# XBee_nRF53240_1_2_may_2022.net
KiCad netlist of a schematic drawn in EAGLE
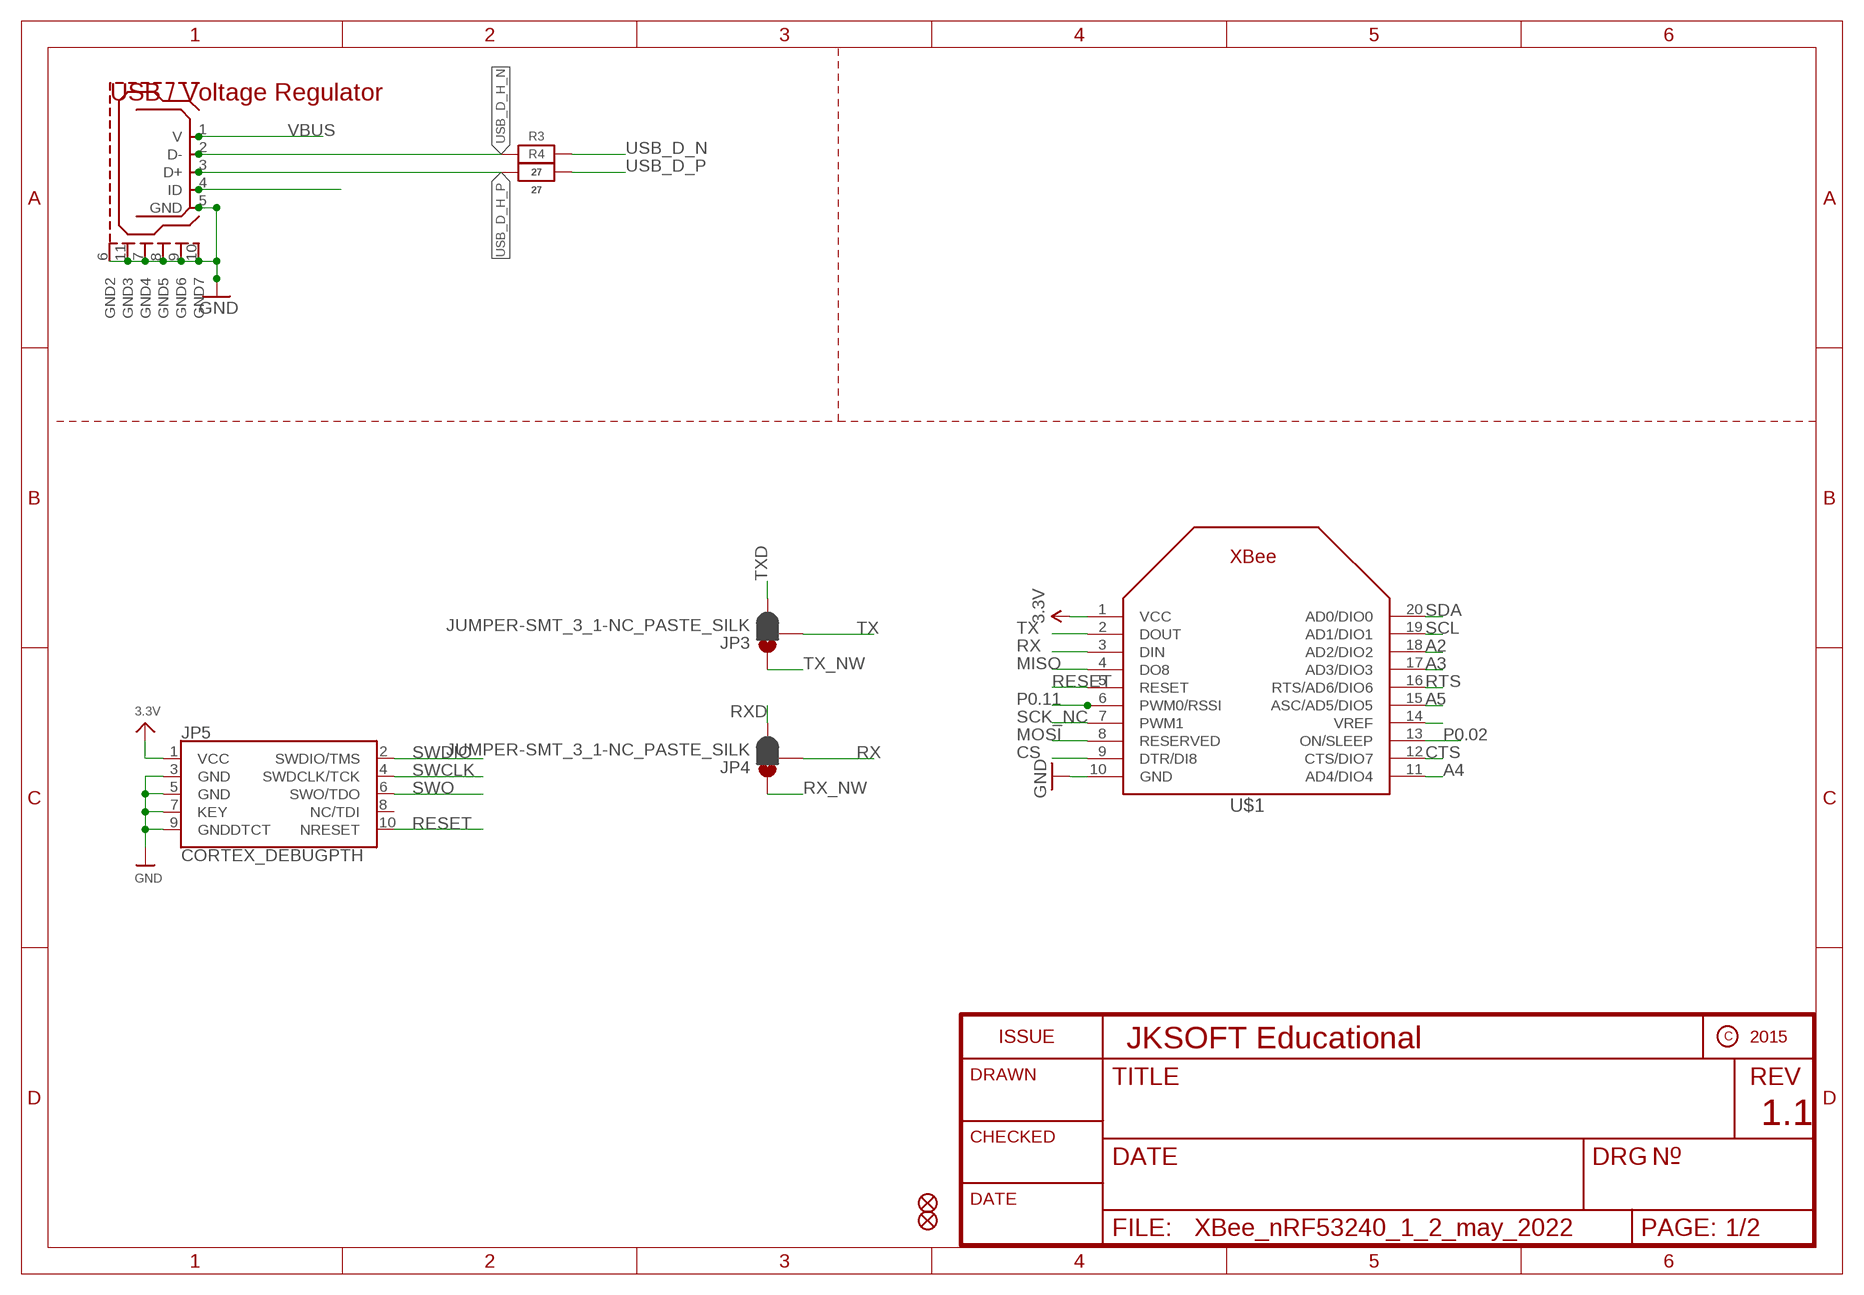
[diagram p0: schematic, sheet 1]
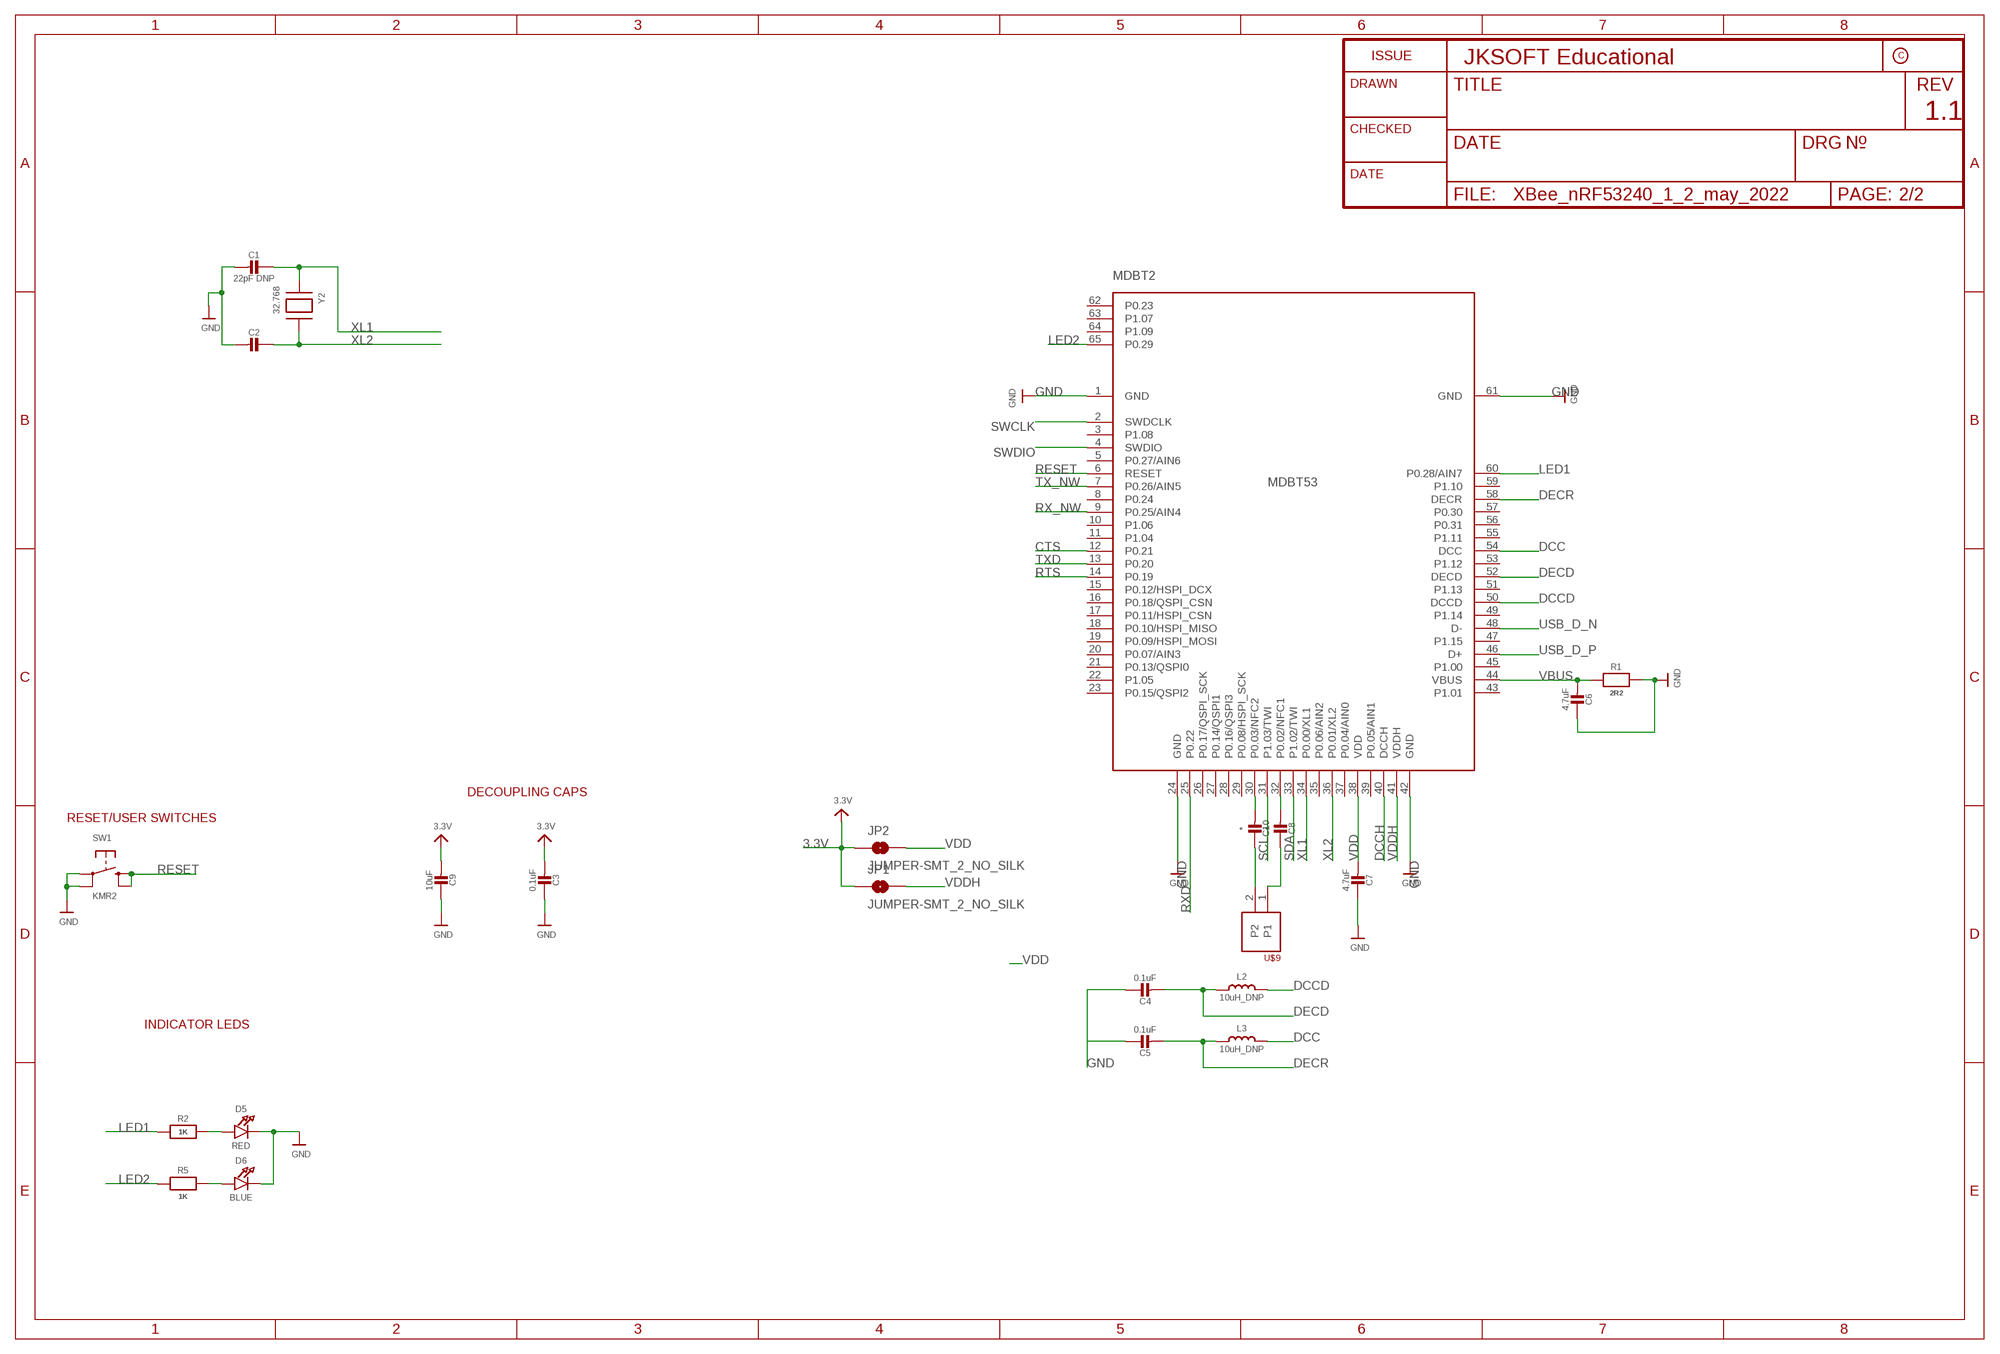
[diagram p1: schematic, sheet 2]

(export (version "E")
  (design (tool "Eeschema 10.0.6"))
  (components
    (comp (ref "C1")
      (value "22pF DNP")
      (footprint "eagle-import:0603-NO")
      (libsource (lib "eagle-import") (part "CAP_CERAMIC0603_NO"))
    )
    (comp (ref "C2")
      (value "22pF DNP")
      (footprint "eagle-import:0603-NO")
      (libsource (lib "eagle-import") (part "CAP_CERAMIC0603_NO"))
    )
    (comp (ref "C3")
      (value "0.1uF")
      (footprint "eagle-import:0603-NO")
      (libsource (lib "eagle-import") (part "CAP_CERAMIC0603_NO"))
    )
    (comp (ref "C4")
      (value "0.1uF")
      (footprint "eagle-import:0603-NO")
      (libsource (lib "eagle-import") (part "CAP_CERAMIC0603_NO"))
    )
    (comp (ref "C5")
      (value "0.1uF")
      (footprint "eagle-import:0603-NO")
      (libsource (lib "eagle-import") (part "CAP_CERAMIC0603_NO"))
    )
    (comp (ref "C6")
      (value "4.7uF")
      (footprint "eagle-import:0805-NO")
      (libsource (lib "eagle-import") (part "CAP_CERAMIC0805-NOOUTLINE"))
    )
    (comp (ref "C7")
      (value "4.7uF")
      (footprint "eagle-import:0805-NO")
      (libsource (lib "eagle-import") (part "CAP_CERAMIC0805-NOOUTLINE"))
    )
    (comp (ref "C8")
      (value "*")
      (footprint "eagle-import:0603-NO")
      (libsource (lib "eagle-import") (part "CAP_CERAMIC0603_NO"))
    )
    (comp (ref "C9")
      (value "10uF")
      (footprint "eagle-import:0805-NO")
      (libsource (lib "eagle-import") (part "CAP_CERAMIC0805-NOOUTLINE"))
    )
    (comp (ref "C10")
      (value "*")
      (footprint "eagle-import:0603-NO")
      (libsource (lib "eagle-import") (part "CAP_CERAMIC0603_NO"))
    )
    (comp (ref "D5")
      (value "RED")
      (footprint "eagle-import:CHIPLED_0805_NOOUTLINE")
      (libsource (lib "eagle-import") (part "LED0805_NOOUTLINE"))
    )
    (comp (ref "D6")
      (value "BLUE")
      (footprint "eagle-import:CHIPLED_0805_NOOUTLINE")
      (libsource (lib "eagle-import") (part "LED0805_NOOUTLINE"))
    )
    (comp (ref "JP1")
      (value "JUMPER-SMT_2_NO_SILK")
      (footprint "eagle-import:SMT-JUMPER_2_NO_SILK")
      (libsource (lib "eagle-import") (part "JUMPER-SMT_2_NO_SILK"))
    )
    (comp (ref "JP2")
      (value "JUMPER-SMT_2_NO_SILK")
      (footprint "eagle-import:SMT-JUMPER_2_NO_SILK")
      (libsource (lib "eagle-import") (part "JUMPER-SMT_2_NO_SILK"))
    )
    (comp (ref "L2")
      (value "10uH_DNP")
      (footprint "eagle-import:_0805MP")
      (libsource (lib "eagle-import") (part "INDUCTOR_0805MP"))
    )
    (comp (ref "L3")
      (value "10uH_DNP")
      (footprint "eagle-import:_0805MP")
      (libsource (lib "eagle-import") (part "INDUCTOR_0805MP"))
    )
    (comp (ref "MDBT2")
      (value "MDBT53")
      (footprint "eagle-import:MDBT53")
      (libsource (lib "eagle-import") (part "MDBT53"))
    )
    (comp (ref "R1")
      (value "2R2")
      (footprint "eagle-import:0603-NO")
      (libsource (lib "eagle-import") (part "RESISTOR_0603_NOOUT"))
    )
    (comp (ref "R2")
      (value "1K")
      (footprint "eagle-import:0603-NO")
      (libsource (lib "eagle-import") (part "RESISTOR_0603_NOOUT"))
    )
    (comp (ref "R5")
      (value "1K")
      (footprint "eagle-import:0603-NO")
      (libsource (lib "eagle-import") (part "RESISTOR_0603_NOOUT"))
    )
    (comp (ref "SW1")
      (value "KMR2")
      (footprint "eagle-import:BTN_KMR2_4.6X2.8")
      (libsource (lib "eagle-import") (part "SWITCH_TACT_SMT4.6X2.8"))
    )
    (comp (ref "U$9")
      (value "PHOENIX_PTSM_M2_TH")
      (footprint "eagle-import:PTSM_M2_THRHOLE")
      (libsource (lib "eagle-import") (part "PHOENIX_PTSM_M2_TH"))
    )
    (comp (ref "Y2")
      (value "32.768")
      (footprint "eagle-import:XTAL3215")
      (libsource (lib "eagle-import") (part "XTAL-3.2X1.5"))
    )
    (comp (ref "FID1")
      (value "FIDUCIAL_1MM")
      (footprint "eagle-import:FIDUCIAL_1MM")
      (libsource (lib "eagle-import") (part "FIDUCIAL_1MM"))
    )
    (comp (ref "FID3")
      (value "FIDUCIAL_1MM")
      (footprint "eagle-import:FIDUCIAL_1MM")
      (libsource (lib "eagle-import") (part "FIDUCIAL_1MM"))
    )
    (comp (ref "JP3")
      (value "JUMPER-SMT_3_1-NC_PASTE_SILK")
      (footprint "eagle-import:SMT-JUMPER_3_1-NC_PASTE_SILK")
      (libsource (lib "eagle-import") (part "JUMPER-SMT_3_1-NC_PASTE_SILK"))
    )
    (comp (ref "JP4")
      (value "JUMPER-SMT_3_1-NC_PASTE_SILK")
      (footprint "eagle-import:SMT-JUMPER_3_1-NC_PASTE_SILK")
      (libsource (lib "eagle-import") (part "JUMPER-SMT_3_1-NC_PASTE_SILK"))
    )
    (comp (ref "JP5")
      (value "CORTEX_DEBUGPTH")
      (footprint "eagle-import:2X5-PTH-1.27MM")
      (libsource (lib "eagle-import") (part "CORTEX_DEBUGPTH"))
    )
    (comp (ref "R3")
      (value "27")
      (footprint "eagle-import:0603-NO")
      (libsource (lib "eagle-import") (part "RESISTOR_0603_NOOUT"))
    )
    (comp (ref "R4")
      (value "27")
      (footprint "eagle-import:0603-NO")
      (libsource (lib "eagle-import") (part "RESISTOR_0603_NOOUT"))
    )
    (comp (ref "U$1")
      (value "XBEE")
      (footprint "eagle-import:XBEE")
      (libsource (lib "eagle-import") (part "XBEE"))
    )
    (comp (ref "U$2")
      (value "USB_MICROB")
      (footprint "eagle-import:USB_MICROB_PACKAGE")
      (libsource (lib "eagle-import") (part "USB_MICROB"))
    )
  )
  (nets
    (net (code "1") (name "3.3V") (class "Default")
      (node (ref "C3") (pin "2") (pinfunction "2_2") (pintype "passive"))
      (node (ref "C9") (pin "2") (pinfunction "2_2") (pintype "passive"))
      (node (ref "JP1") (pin "1") (pinfunction "1_1") (pintype "passive"))
      (node (ref "JP2") (pin "1") (pinfunction "1_1") (pintype "passive"))
      (node (ref "JP5") (pin "1") (pinfunction "VCC_1") (pintype "bidirectional"))
      (node (ref "U$1") (pin "1") (pinfunction "VCC_1") (pintype "power_in"))
    )
    (net (code "2") (name "A2") (class "Default")
      (node (ref "U$1") (pin "18") (pinfunction "AD2/DIO2_18") (pintype "bidirectional"))
    )
    (net (code "3") (name "A3") (class "Default")
      (node (ref "U$1") (pin "17") (pinfunction "AD3/DIO3_17") (pintype "bidirectional"))
    )
    (net (code "4") (name "A4") (class "Default")
      (node (ref "U$1") (pin "11") (pinfunction "AD4/DIO4_11") (pintype "bidirectional"))
    )
    (net (code "5") (name "A5") (class "Default")
      (node (ref "U$1") (pin "15") (pinfunction "ASC/AD5/DIO5_15") (pintype "bidirectional"))
    )
    (net (code "6") (name "CS") (class "Default")
      (node (ref "U$1") (pin "9") (pinfunction "DTR/DI8_9") (pintype "input"))
    )
    (net (code "7") (name "CTS") (class "Default")
      (node (ref "MDBT2") (pin "12") (pinfunction "P0.21_12") (pintype "bidirectional"))
      (node (ref "U$1") (pin "12") (pinfunction "CTS/DIO7_12") (pintype "bidirectional"))
    )
    (net (code "8") (name "DCC") (class "Default")
      (node (ref "L3") (pin "2") (pinfunction "2_2") (pintype "passive"))
      (node (ref "MDBT2") (pin "54") (pinfunction "DCC_54") (pintype "bidirectional"))
    )
    (net (code "9") (name "DCCD") (class "Default")
      (node (ref "L2") (pin "2") (pinfunction "2_2") (pintype "passive"))
      (node (ref "MDBT2") (pin "50") (pinfunction "DCCD_50") (pintype "bidirectional"))
    )
    (net (code "10") (name "DCCH") (class "Default")
      (node (ref "MDBT2") (pin "40") (pinfunction "DCCH_40") (pintype "bidirectional"))
    )
    (net (code "11") (name "DECD") (class "Default")
      (node (ref "C4") (pin "2") (pinfunction "2_2") (pintype "passive"))
      (node (ref "L2") (pin "1") (pinfunction "1_1") (pintype "passive"))
      (node (ref "MDBT2") (pin "52") (pinfunction "DECD_52") (pintype "bidirectional"))
    )
    (net (code "12") (name "DECR") (class "Default")
      (node (ref "C5") (pin "2") (pinfunction "2_2") (pintype "passive"))
      (node (ref "L3") (pin "1") (pinfunction "1_1") (pintype "passive"))
      (node (ref "MDBT2") (pin "58") (pinfunction "DECR_58") (pintype "bidirectional"))
    )
    (net (code "13") (name "GND") (class "Default")
      (node (ref "C1") (pin "2") (pinfunction "2_2") (pintype "passive"))
      (node (ref "C2") (pin "2") (pinfunction "2_2") (pintype "passive"))
      (node (ref "C3") (pin "1") (pinfunction "1_1") (pintype "passive"))
      (node (ref "C4") (pin "1") (pinfunction "1_1") (pintype "passive"))
      (node (ref "C6") (pin "1") (pinfunction "1_1") (pintype "passive"))
      (node (ref "C7") (pin "1") (pinfunction "1_1") (pintype "passive"))
      (node (ref "C9") (pin "1") (pinfunction "1_1") (pintype "passive"))
      (node (ref "D5") (pin "C") (pinfunction "C_C") (pintype "passive"))
      (node (ref "D6") (pin "C") (pinfunction "C_C") (pintype "passive"))
      (node (ref "JP5") (pin "3") (pinfunction "GND_3") (pintype "bidirectional"))
      (node (ref "JP5") (pin "5") (pinfunction "GND_5") (pintype "bidirectional"))
      (node (ref "JP5") (pin "7") (pinfunction "KEY_7") (pintype "bidirectional"))
      (node (ref "JP5") (pin "9") (pinfunction "GNDDTCT_9") (pintype "bidirectional"))
      (node (ref "MDBT2") (pin "1") (pinfunction "GND_1") (pintype "bidirectional"))
      (node (ref "MDBT2") (pin "24") (pinfunction "GND_24") (pintype "bidirectional"))
      (node (ref "MDBT2") (pin "42") (pinfunction "GND_42") (pintype "bidirectional"))
      (node (ref "MDBT2") (pin "61") (pinfunction "GND_61") (pintype "bidirectional"))
      (node (ref "R1") (pin "2") (pinfunction "2_2") (pintype "passive"))
      (node (ref "SW1") (pin "A") (pinfunction "P_A") (pintype "passive"))
      (node (ref "SW1") (pin "A'") (pinfunction "P1_A'") (pintype "passive"))
      (node (ref "U$1") (pin "10") (pinfunction "GND_10") (pintype "power_in"))
      (node (ref "U$2") (pin "10") (pinfunction "GND7_10") (pintype "bidirectional"))
      (node (ref "U$2") (pin "11") (pinfunction "GND3_11") (pintype "bidirectional"))
      (node (ref "U$2") (pin "5") (pinfunction "GND_5") (pintype "bidirectional"))
      (node (ref "U$2") (pin "6") (pinfunction "GND2_6") (pintype "bidirectional"))
      (node (ref "U$2") (pin "7") (pinfunction "GND4_7") (pintype "bidirectional"))
      (node (ref "U$2") (pin "8") (pinfunction "GND5_8") (pintype "bidirectional"))
      (node (ref "U$2") (pin "9") (pinfunction "GND6_9") (pintype "bidirectional"))
    )
    (net (code "14") (name "LED1") (class "Default")
      (node (ref "MDBT2") (pin "60") (pinfunction "P0.28/AIN7_60") (pintype "bidirectional"))
      (node (ref "R2") (pin "1") (pinfunction "1_1") (pintype "passive"))
    )
    (net (code "15") (name "LED2") (class "Default")
      (node (ref "MDBT2") (pin "65") (pinfunction "P0.29_65") (pintype "bidirectional"))
      (node (ref "R5") (pin "1") (pinfunction "1_1") (pintype "passive"))
    )
    (net (code "16") (name "MISO") (class "Default")
      (node (ref "U$1") (pin "4") (pinfunction "DO8_4") (pintype "output"))
    )
    (net (code "18") (name "MOSI") (class "Default")
      (node (ref "U$1") (pin "8") (pinfunction "RESERVED_8") (pintype "no_connect"))
    )
    (net (code "19") (name "Net-(D5-PadA)") (class "Default")
      (node (ref "D5") (pin "A") (pinfunction "A_A") (pintype "passive"))
      (node (ref "R2") (pin "2") (pinfunction "2_2") (pintype "passive"))
    )
    (net (code "20") (name "Net-(D6-PadA)") (class "Default")
      (node (ref "D6") (pin "A") (pinfunction "A_A") (pintype "passive"))
      (node (ref "R5") (pin "2") (pinfunction "2_2") (pintype "passive"))
    )
    (net (code "21") (name "Net-(MDBT2-P0.02{slash}NFC1)") (class "Default")
      (node (ref "C8") (pin "2") (pinfunction "2_2") (pintype "passive"))
      (node (ref "MDBT2") (pin "32") (pinfunction "P0.02/NFC1_32") (pintype "bidirectional"))
    )
    (net (code "22") (name "Net-(MDBT2-P0.03{slash}NFC2)") (class "Default")
      (node (ref "C10") (pin "2") (pinfunction "2_2") (pintype "passive"))
      (node (ref "MDBT2") (pin "30") (pinfunction "P0.03/NFC2_30") (pintype "bidirectional"))
    )
    (net (code "23") (name "Net-(U$9-P1)") (class "Default")
      (node (ref "C8") (pin "1") (pinfunction "1_1") (pintype "passive"))
      (node (ref "U$9") (pin "1") (pinfunction "P1_1") (pintype "bidirectional"))
    )
    (net (code "24") (name "Net-(U$9-P2)") (class "Default")
      (node (ref "C10") (pin "1") (pinfunction "1_1") (pintype "passive"))
      (node (ref "U$9") (pin "2") (pinfunction "P2_2") (pintype "bidirectional"))
    )
    (net (code "25") (name "P0.02") (class "Default")
      (node (ref "U$1") (pin "13") (pinfunction "ON/SLEEP_13") (pintype "output"))
    )
    (net (code "26") (name "P0.11") (class "Default")
      (node (ref "U$1") (pin "6") (pinfunction "PWM0/RSSI_6") (pintype "output"))
    )
    (net (code "27") (name "RESET") (class "Default")
      (node (ref "JP5") (pin "10") (pinfunction "NRESET_10") (pintype "bidirectional"))
      (node (ref "MDBT2") (pin "6") (pinfunction "RESET_6") (pintype "bidirectional"))
      (node (ref "SW1") (pin "B") (pinfunction "S_B") (pintype "passive"))
      (node (ref "SW1") (pin "B'") (pinfunction "S1_B'") (pintype "passive"))
      (node (ref "U$1") (pin "5") (pinfunction "RESET_5") (pintype "input"))
    )
    (net (code "28") (name "RTS") (class "Default")
      (node (ref "MDBT2") (pin "14") (pinfunction "P0.19_14") (pintype "bidirectional"))
      (node (ref "U$1") (pin "16") (pinfunction "RTS/AD6/DIO6_16") (pintype "bidirectional"))
    )
    (net (code "29") (name "RX") (class "Default")
      (node (ref "JP4") (pin "2") (pinfunction "2_2") (pintype "passive"))
      (node (ref "U$1") (pin "3") (pinfunction "DIN_3") (pintype "input"))
    )
    (net (code "30") (name "RXD") (class "Default")
      (node (ref "JP4") (pin "3") (pinfunction "3_3") (pintype "passive"))
      (node (ref "MDBT2") (pin "25") (pinfunction "P0.22_25") (pintype "bidirectional"))
    )
    (net (code "31") (name "RX_NW") (class "Default")
      (node (ref "JP4") (pin "1") (pinfunction "1_1") (pintype "passive"))
      (node (ref "MDBT2") (pin "9") (pinfunction "P0.25/AIN4_9") (pintype "bidirectional"))
    )
    (net (code "32") (name "SCK_NC") (class "Default")
      (node (ref "U$1") (pin "7") (pinfunction "PWM1_7") (pintype "output"))
    )
    (net (code "33") (name "SCL") (class "Default")
      (node (ref "MDBT2") (pin "31") (pinfunction "P1.03/TWI_31") (pintype "bidirectional"))
      (node (ref "U$1") (pin "19") (pinfunction "AD1/DIO1_19") (pintype "bidirectional"))
    )
    (net (code "34") (name "SDA") (class "Default")
      (node (ref "MDBT2") (pin "33") (pinfunction "P1.02/TWI_33") (pintype "bidirectional"))
      (node (ref "U$1") (pin "20") (pinfunction "AD0/DIO0_20") (pintype "bidirectional"))
    )
    (net (code "35") (name "SWCLK") (class "Default")
      (node (ref "JP5") (pin "4") (pinfunction "SWDCLK/TCK_4") (pintype "bidirectional"))
      (node (ref "MDBT2") (pin "2") (pinfunction "SWDCLK_2") (pintype "bidirectional"))
    )
    (net (code "36") (name "SWDIO") (class "Default")
      (node (ref "JP5") (pin "2") (pinfunction "SWDIO/TMS_2") (pintype "bidirectional"))
      (node (ref "MDBT2") (pin "4") (pinfunction "SWDIO_4") (pintype "bidirectional"))
    )
    (net (code "37") (name "SWO") (class "Default")
      (node (ref "JP5") (pin "6") (pinfunction "SWO/TDO_6") (pintype "bidirectional"))
    )
    (net (code "38") (name "TX") (class "Default")
      (node (ref "JP3") (pin "2") (pinfunction "2_2") (pintype "passive"))
      (node (ref "U$1") (pin "2") (pinfunction "DOUT_2") (pintype "output"))
    )
    (net (code "39") (name "TXD") (class "Default")
      (node (ref "JP3") (pin "3") (pinfunction "3_3") (pintype "passive"))
      (node (ref "MDBT2") (pin "13") (pinfunction "P0.20_13") (pintype "bidirectional"))
    )
    (net (code "40") (name "TX_NW") (class "Default")
      (node (ref "JP3") (pin "1") (pinfunction "1_1") (pintype "passive"))
      (node (ref "MDBT2") (pin "7") (pinfunction "P0.26/AIN5_7") (pintype "bidirectional"))
    )
    (net (code "41") (name "USB_D_H_N") (class "Default")
      (node (ref "R3") (pin "1") (pinfunction "1_1") (pintype "passive"))
      (node (ref "U$2") (pin "2") (pinfunction "D-_2") (pintype "bidirectional"))
    )
    (net (code "42") (name "USB_D_H_P") (class "Default")
      (node (ref "R4") (pin "1") (pinfunction "1_1") (pintype "passive"))
      (node (ref "U$2") (pin "3") (pinfunction "D+_3") (pintype "bidirectional"))
    )
    (net (code "43") (name "USB_D_N") (class "Default")
      (node (ref "MDBT2") (pin "48") (pinfunction "D-_48") (pintype "bidirectional"))
      (node (ref "R3") (pin "2") (pinfunction "2_2") (pintype "passive"))
    )
    (net (code "44") (name "USB_D_P") (class "Default")
      (node (ref "MDBT2") (pin "46") (pinfunction "D+_46") (pintype "bidirectional"))
      (node (ref "R4") (pin "2") (pinfunction "2_2") (pintype "passive"))
    )
    (net (code "45") (name "VBUS") (class "Default")
      (node (ref "C6") (pin "2") (pinfunction "2_2") (pintype "passive"))
      (node (ref "MDBT2") (pin "44") (pinfunction "VBUS_44") (pintype "bidirectional"))
      (node (ref "R1") (pin "1") (pinfunction "1_1") (pintype "passive"))
      (node (ref "U$2") (pin "1") (pinfunction "V_1") (pintype "bidirectional"))
    )
    (net (code "46") (name "VDD") (class "Default")
      (node (ref "C7") (pin "2") (pinfunction "2_2") (pintype "passive"))
      (node (ref "JP2") (pin "2") (pinfunction "2_2") (pintype "passive"))
      (node (ref "MDBT2") (pin "38") (pinfunction "VDD_38") (pintype "bidirectional"))
    )
    (net (code "47") (name "VDDH") (class "Default")
      (node (ref "JP1") (pin "2") (pinfunction "2_2") (pintype "passive"))
      (node (ref "MDBT2") (pin "41") (pinfunction "VDDH_41") (pintype "bidirectional"))
    )
    (net (code "48") (name "XL1") (class "Default")
      (node (ref "C1") (pin "1") (pinfunction "1_1") (pintype "passive"))
      (node (ref "MDBT2") (pin "34") (pinfunction "P0.00/XL1_34") (pintype "bidirectional"))
      (node (ref "Y2") (pin "P$1") (pinfunction "P$1_P$1") (pintype "bidirectional"))
    )
    (net (code "49") (name "XL2") (class "Default")
      (node (ref "C2") (pin "1") (pinfunction "1_1") (pintype "passive"))
      (node (ref "MDBT2") (pin "36") (pinfunction "P0.01/XL2_36") (pintype "bidirectional"))
      (node (ref "Y2") (pin "P$2") (pinfunction "P$2_P$2") (pintype "bidirectional"))
    )
    (net (code "50") (name "unconnected-(C5-Pad1)") (class "Default")
      (node (ref "C5") (pin "1") (pinfunction "1_1") (pintype "passive"))
    )
    (net (code "51") (name "unconnected-(JP5-NC{slash}TDI-Pad8)") (class "Default")
      (node (ref "JP5") (pin "8") (pinfunction "NC/TDI_8") (pintype "bidirectional"))
    )
    (net (code "52") (name "unconnected-(MDBT2-P0.04{slash}AIN0-Pad37)") (class "Default")
      (node (ref "MDBT2") (pin "37") (pinfunction "P0.04/AIN0_37") (pintype "bidirectional"))
    )
    (net (code "53") (name "unconnected-(MDBT2-P0.05{slash}AIN1-Pad39)") (class "Default")
      (node (ref "MDBT2") (pin "39") (pinfunction "P0.05/AIN1_39") (pintype "bidirectional"))
    )
    (net (code "54") (name "unconnected-(MDBT2-P0.06{slash}AIN2-Pad35)") (class "Default")
      (node (ref "MDBT2") (pin "35") (pinfunction "P0.06/AIN2_35") (pintype "bidirectional"))
    )
    (net (code "55") (name "unconnected-(MDBT2-P0.07{slash}AIN3-Pad20)") (class "Default")
      (node (ref "MDBT2") (pin "20") (pinfunction "P0.07/AIN3_20") (pintype "bidirectional"))
    )
    (net (code "56") (name "unconnected-(MDBT2-P0.08{slash}HSPI_SCK-Pad29)") (class "Default")
      (node (ref "MDBT2") (pin "29") (pinfunction "P0.08/HSPI_SCK_29") (pintype "bidirectional"))
    )
    (net (code "57") (name "unconnected-(MDBT2-P0.09{slash}HSPI_MOSI-Pad19)") (class "Default")
      (node (ref "MDBT2") (pin "19") (pinfunction "P0.09/HSPI_MOSI_19") (pintype "bidirectional"))
    )
    (net (code "58") (name "unconnected-(MDBT2-P0.10{slash}HSPI_MISO-Pad18)") (class "Default")
      (node (ref "MDBT2") (pin "18") (pinfunction "P0.10/HSPI_MISO_18") (pintype "bidirectional"))
    )
    (net (code "59") (name "unconnected-(MDBT2-P0.11{slash}HSPI_CSN-Pad17)") (class "Default")
      (node (ref "MDBT2") (pin "17") (pinfunction "P0.11/HSPI_CSN_17") (pintype "bidirectional"))
    )
    (net (code "60") (name "unconnected-(MDBT2-P0.12{slash}HSPI_DCX-Pad15)") (class "Default")
      (node (ref "MDBT2") (pin "15") (pinfunction "P0.12/HSPI_DCX_15") (pintype "bidirectional"))
    )
    (net (code "61") (name "unconnected-(MDBT2-P0.13{slash}QSPI0-Pad21)") (class "Default")
      (node (ref "MDBT2") (pin "21") (pinfunction "P0.13/QSPI0_21") (pintype "bidirectional"))
    )
    (net (code "62") (name "unconnected-(MDBT2-P0.14{slash}QSPI1-Pad27)") (class "Default")
      (node (ref "MDBT2") (pin "27") (pinfunction "P0.14/QSPI1_27") (pintype "bidirectional"))
    )
    (net (code "63") (name "unconnected-(MDBT2-P0.15{slash}QSPI2-Pad23)") (class "Default")
      (node (ref "MDBT2") (pin "23") (pinfunction "P0.15/QSPI2_23") (pintype "bidirectional"))
    )
    (net (code "64") (name "unconnected-(MDBT2-P0.16{slash}QSPI3-Pad28)") (class "Default")
      (node (ref "MDBT2") (pin "28") (pinfunction "P0.16/QSPI3_28") (pintype "bidirectional"))
    )
    (net (code "65") (name "unconnected-(MDBT2-P0.17{slash}QSPI_SCK-Pad26)") (class "Default")
      (node (ref "MDBT2") (pin "26") (pinfunction "P0.17/QSPI_SCK_26") (pintype "bidirectional"))
    )
    (net (code "66") (name "unconnected-(MDBT2-P0.18{slash}QSPI_CSN-Pad16)") (class "Default")
      (node (ref "MDBT2") (pin "16") (pinfunction "P0.18/QSPI_CSN_16") (pintype "bidirectional"))
    )
    (net (code "67") (name "unconnected-(MDBT2-P0.23-Pad62)") (class "Default")
      (node (ref "MDBT2") (pin "62") (pinfunction "P0.23_62") (pintype "bidirectional"))
    )
    (net (code "68") (name "unconnected-(MDBT2-P0.24-Pad8)") (class "Default")
      (node (ref "MDBT2") (pin "8") (pinfunction "P0.24_8") (pintype "bidirectional"))
    )
    (net (code "69") (name "unconnected-(MDBT2-P0.27{slash}AIN6-Pad5)") (class "Default")
      (node (ref "MDBT2") (pin "5") (pinfunction "P0.27/AIN6_5") (pintype "bidirectional"))
    )
    (net (code "70") (name "unconnected-(MDBT2-P0.30-Pad57)") (class "Default")
      (node (ref "MDBT2") (pin "57") (pinfunction "P0.30_57") (pintype "bidirectional"))
    )
    (net (code "71") (name "unconnected-(MDBT2-P0.31-Pad56)") (class "Default")
      (node (ref "MDBT2") (pin "56") (pinfunction "P0.31_56") (pintype "bidirectional"))
    )
    (net (code "72") (name "unconnected-(MDBT2-P1.00-Pad45)") (class "Default")
      (node (ref "MDBT2") (pin "45") (pinfunction "P1.00_45") (pintype "bidirectional"))
    )
    (net (code "73") (name "unconnected-(MDBT2-P1.01-Pad43)") (class "Default")
      (node (ref "MDBT2") (pin "43") (pinfunction "P1.01_43") (pintype "bidirectional"))
    )
    (net (code "74") (name "unconnected-(MDBT2-P1.04-Pad11)") (class "Default")
      (node (ref "MDBT2") (pin "11") (pinfunction "P1.04_11") (pintype "bidirectional"))
    )
    (net (code "75") (name "unconnected-(MDBT2-P1.05-Pad22)") (class "Default")
      (node (ref "MDBT2") (pin "22") (pinfunction "P1.05_22") (pintype "bidirectional"))
    )
    (net (code "76") (name "unconnected-(MDBT2-P1.06-Pad10)") (class "Default")
      (node (ref "MDBT2") (pin "10") (pinfunction "P1.06_10") (pintype "bidirectional"))
    )
    (net (code "77") (name "unconnected-(MDBT2-P1.07-Pad63)") (class "Default")
      (node (ref "MDBT2") (pin "63") (pinfunction "P1.07_63") (pintype "bidirectional"))
    )
    (net (code "78") (name "unconnected-(MDBT2-P1.08-Pad3)") (class "Default")
      (node (ref "MDBT2") (pin "3") (pinfunction "P1.08_3") (pintype "bidirectional"))
    )
    (net (code "79") (name "unconnected-(MDBT2-P1.09-Pad64)") (class "Default")
      (node (ref "MDBT2") (pin "64") (pinfunction "P1.09_64") (pintype "bidirectional"))
    )
    (net (code "80") (name "unconnected-(MDBT2-P1.10-Pad59)") (class "Default")
      (node (ref "MDBT2") (pin "59") (pinfunction "P1.10_59") (pintype "bidirectional"))
    )
    (net (code "81") (name "unconnected-(MDBT2-P1.11-Pad55)") (class "Default")
      (node (ref "MDBT2") (pin "55") (pinfunction "P1.11_55") (pintype "bidirectional"))
    )
    (net (code "82") (name "unconnected-(MDBT2-P1.12-Pad53)") (class "Default")
      (node (ref "MDBT2") (pin "53") (pinfunction "P1.12_53") (pintype "bidirectional"))
    )
    (net (code "83") (name "unconnected-(MDBT2-P1.13-Pad51)") (class "Default")
      (node (ref "MDBT2") (pin "51") (pinfunction "P1.13_51") (pintype "bidirectional"))
    )
    (net (code "84") (name "unconnected-(MDBT2-P1.14-Pad49)") (class "Default")
      (node (ref "MDBT2") (pin "49") (pinfunction "P1.14_49") (pintype "bidirectional"))
    )
    (net (code "85") (name "unconnected-(MDBT2-P1.15-Pad47)") (class "Default")
      (node (ref "MDBT2") (pin "47") (pinfunction "P1.15_47") (pintype "bidirectional"))
    )
    (net (code "86") (name "unconnected-(U$1-VREF-Pad14)") (class "Default")
      (node (ref "U$1") (pin "14") (pinfunction "VREF_14") (pintype "input"))
    )
    (net (code "87") (name "unconnected-(U$2-ID-Pad4)") (class "Default")
      (node (ref "U$2") (pin "4") (pinfunction "ID_4") (pintype "bidirectional"))
    )
  )
)
